# Sheet1.net
KiCad netlist of a schematic drawn in Altium Designer
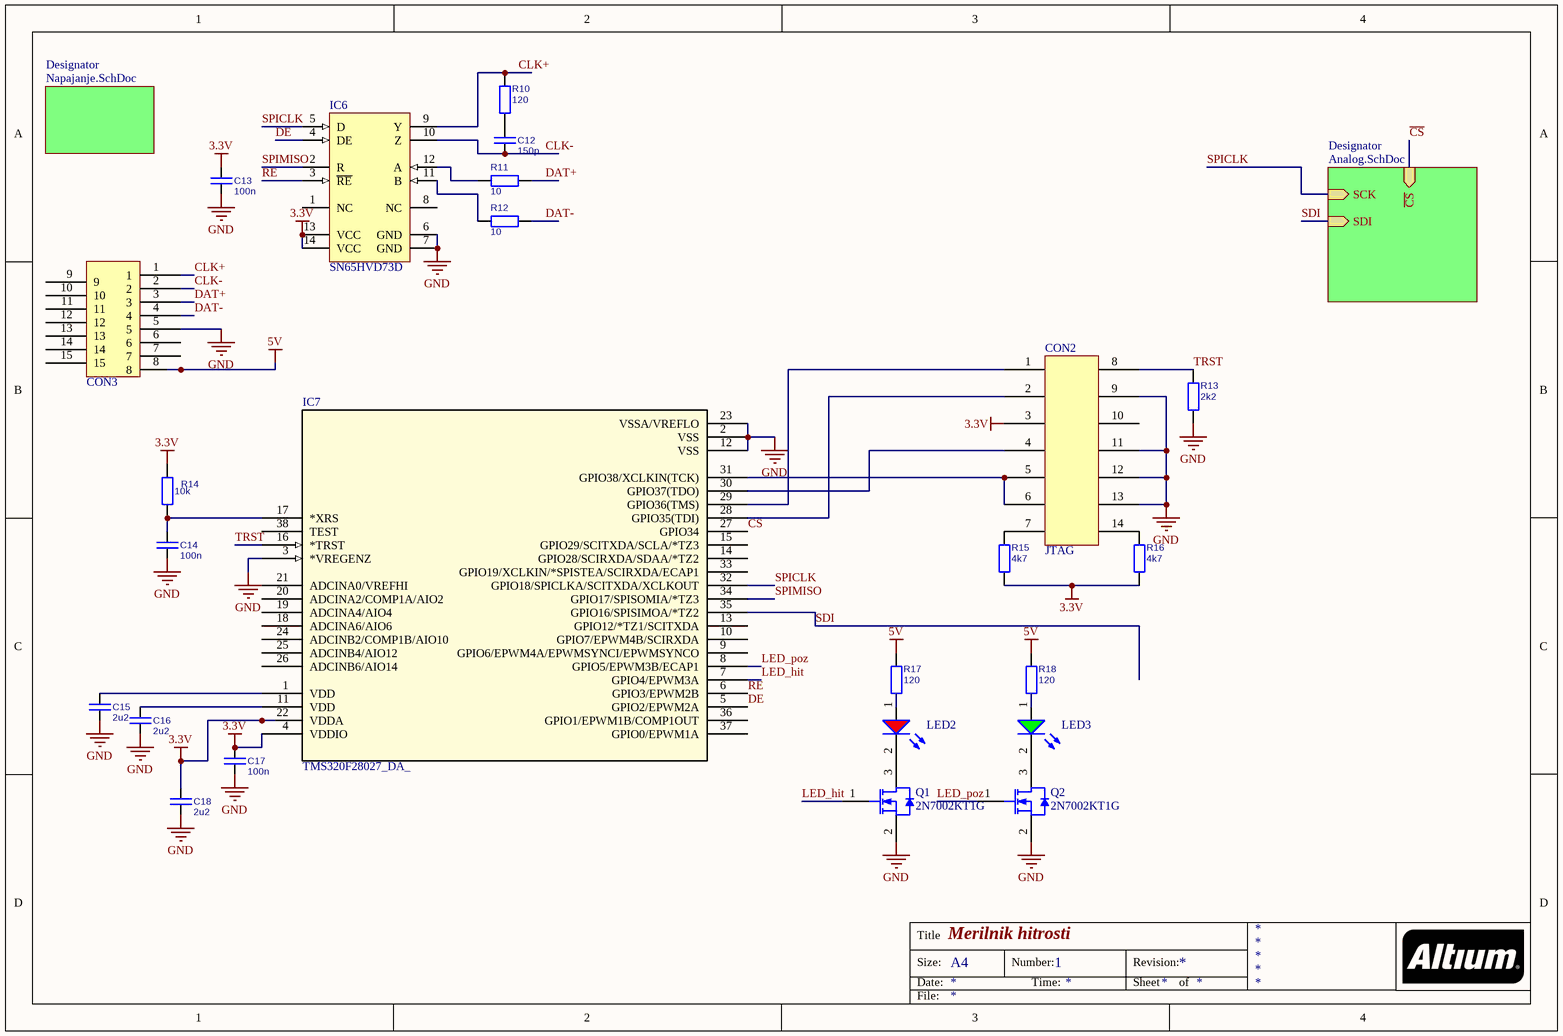
[diagram p0: Sheet1.SchDoc]

(export (version "E")
  (design (tool "Eeschema 10.0.6"))
  (components
    (comp (ref "C12")
      (value "150p")
      (footprint "C0603")
      (description "Capacitor")
      (libsource (lib "General") (part "C"))
    )
    (comp (ref "C13")
      (value "100n")
      (footprint "C0603")
      (description "Capacitor")
      (libsource (lib "General") (part "C"))
    )
    (comp (ref "C14")
      (value "100n")
      (footprint "C0603")
      (description "Capacitor")
      (libsource (lib "General") (part "C"))
    )
    (comp (ref "C15")
      (value "2u2")
      (footprint "C0603")
      (description "Capacitor")
      (libsource (lib "General") (part "C"))
    )
    (comp (ref "C16")
      (value "2u2")
      (footprint "C0603")
      (description "Capacitor")
      (libsource (lib "General") (part "C"))
    )
    (comp (ref "C17")
      (value "100n")
      (footprint "C0603")
      (description "Capacitor")
      (libsource (lib "General") (part "C"))
    )
    (comp (ref "C18")
      (value "2u2")
      (footprint "C0603")
      (description "Capacitor")
      (libsource (lib "General") (part "C"))
    )
    (comp (ref "CON2")
      (value "JTAG")
      (footprint "JTAG micromatch")
      (libsource (lib "2016-11-04_16-51-30") (part "JTAG"))
    )
    (comp (ref "CON3")
      (value "DSUbConector")
      (footprint "DSUB conector")
      (libsource (lib "2016-11-04_16-51-30") (part "DSUbConector"))
    )
    (comp (ref "IC6")
      (value "SN65HVD73D")
      (footprint "D14_N")
      (fields (field (name "MANUFACTURER") "Texas Instruments") (field (name "PARTNUMBER") "SN65HVD55DR"))
      (libsource (lib "Texas Instruments Interface RS-485") (part "SN65HVD55DR"))
    )
    (comp (ref "IC7")
      (value "TMS320F28027_DA_")
      (footprint "TSOP65P810X120-38N")
      (description "Imported")
      (fields (field (name "MANUFACTURER_PART_NUMBER") "tms320f28027_da_38"))
      (libsource (lib "2016-11-04_16-51-30") (part "TMS320F28027_DA_"))
    )
    (comp (ref "LED2")
      (value "150060RS75000")
      (footprint "LED_0603_Red")
      (description "SMD mono-color Chip LED, WL-SMCW, Red")
      (fields
        (field (name "MANUFACTURER") "W黵th Elektronik eiSos GmbH")
        (field (name "CREATED BY") "Christin Otto")
      )
      (libsource (lib "WL-SMCW_rev15b") (part "WL-SMCW 0603  150060RS75000"))
    )
    (comp (ref "LED3")
      (value "150060VS75000")
      (footprint "LED_0603_Bright Green")
      (description "SMD mono-color Chip LED, WL-SMCW, Bright Green")
      (fields
        (field (name "MANUFACTURER") "W黵th Elektronik eiSos GmbH")
        (field (name "CREATED BY") "Christin Otto")
      )
      (libsource (lib "WL-SMCW_rev15b") (part "WL-SMCW 0603  150060VS75000"))
    )
    (comp (ref "Q1")
      (value "2N7002KT1G")
      (footprint "NXP-SOT23_N")
      (description "N-Channel Enhancement Mode Field-Effect Transistor, 50 V, 0.173 A, 3-Pin SOT23, Tape and Reel")
      (libsource (lib "NXP Semiconductors Standard MOSFETs") (part "BSN20,215"))
    )
    (comp (ref "Q2")
      (value "2N7002KT1G")
      (footprint "NXP-SOT23_N")
      (description "N-Channel Enhancement Mode Field-Effect Transistor, 50 V, 0.173 A, 3-Pin SOT23, Tape and Reel")
      (libsource (lib "NXP Semiconductors Standard MOSFETs") (part "BSN20,215"))
    )
    (comp (ref "R10")
      (value "120")
      (footprint "R0603")
      (description "R")
      (libsource (lib "General") (part "R"))
    )
    (comp (ref "R11")
      (value "10")
      (footprint "R0603")
      (description "R")
      (libsource (lib "General") (part "R"))
    )
    (comp (ref "R12")
      (value "10")
      (footprint "R0603")
      (description "R")
      (libsource (lib "General") (part "R"))
    )
    (comp (ref "R13")
      (value "2k2")
      (footprint "R0805")
      (description "R")
      (fields (field (name "Comment") "120"))
      (libsource (lib "General") (part "R"))
    )
    (comp (ref "R14")
      (value "10k")
      (footprint "R0805")
      (description "R")
      (fields (field (name "Comment") "120"))
      (libsource (lib "General") (part "R"))
    )
    (comp (ref "R15")
      (value "4k7")
      (footprint "R0805")
      (description "R")
      (libsource (lib "General") (part "R"))
    )
    (comp (ref "R16")
      (value "4k7")
      (footprint "R0805")
      (description "R")
      (libsource (lib "General") (part "R"))
    )
    (comp (ref "R17")
      (value "120")
      (footprint "R0805")
      (description "R")
      (libsource (lib "General") (part "R"))
    )
    (comp (ref "R18")
      (value "120")
      (footprint "R0805")
      (description "R")
      (libsource (lib "General") (part "R"))
    )
  )
  (nets
    (net (code "1") (name "/CLK+") (class "Default")
      (node (ref "CON3") (pin "1") (pinfunction "1_1") (pintype "passive"))
      (node (ref "IC6") (pin "9") (pinfunction "Y_9") (pintype "tri_state"))
      (node (ref "R10") (pin "1") (pintype "passive"))
    )
    (net (code "2") (name "/CLK-") (class "Default")
      (node (ref "C12") (pin "2") (pinfunction "2_2") (pintype "passive"))
      (node (ref "CON3") (pin "2") (pinfunction "2_2") (pintype "passive"))
      (node (ref "IC6") (pin "10") (pinfunction "Z_10") (pintype "tri_state"))
    )
    (net (code "3") (name "/DAT+") (class "Default")
      (node (ref "CON3") (pin "3") (pinfunction "3_3") (pintype "passive"))
      (node (ref "R11") (pin "1") (pintype "passive"))
    )
    (net (code "4") (name "/DAT-") (class "Default")
      (node (ref "CON3") (pin "4") (pinfunction "4_4") (pintype "passive"))
      (node (ref "R12") (pin "1") (pintype "passive"))
    )
    (net (code "5") (name "/DE") (class "Default")
      (node (ref "IC6") (pin "4") (pinfunction "DE_4") (pintype "input"))
      (node (ref "IC7") (pin "5") (pinfunction "GPIO2/EPWM2A_5") (pintype "passive"))
    )
    (net (code "6") (name "/LED_hit") (class "Default")
      (node (ref "IC7") (pin "7") (pinfunction "GPIO4/EPWM3A_7") (pintype "passive"))
      (node (ref "Q1") (pin "1") (pinfunction "G_1") (pintype "passive"))
    )
    (net (code "7") (name "/LED_poz") (class "Default")
      (node (ref "IC7") (pin "8") (pinfunction "GPIO5/EPWM3B/ECAP1_8") (pintype "passive"))
      (node (ref "Q2") (pin "1") (pinfunction "G_1") (pintype "passive"))
    )
    (net (code "8") (name "/RE") (class "Default")
      (node (ref "IC6") (pin "3") (pinfunction "~{RE}_3") (pintype "input"))
      (node (ref "IC7") (pin "6") (pinfunction "GPIO3/EPWM2B_6") (pintype "passive"))
    )
    (net (code "9") (name "/SDI") (class "Default")
      (node (ref "IC7") (pin "35") (pinfunction "GPIO16/SPISIMOA/*TZ2_35") (pintype "passive"))
    )
    (net (code "10") (name "/SPICLK") (class "Default")
      (node (ref "IC6") (pin "5") (pinfunction "D_5") (pintype "input"))
      (node (ref "IC7") (pin "32") (pinfunction "GPIO18/SPICLKA/SCITXDA/XCLKOUT_32") (pintype "passive"))
    )
    (net (code "11") (name "/SPIMISO") (class "Default")
      (node (ref "IC6") (pin "2") (pinfunction "R_2") (pintype "tri_state"))
      (node (ref "IC7") (pin "34") (pinfunction "GPIO17/SPISOMIA/*TZ3_34") (pintype "passive"))
    )
    (net (code "12") (name "/TRST") (class "Default")
      (node (ref "CON2") (pin "8") (pinfunction "8_8") (pintype "passive"))
      (node (ref "IC7") (pin "16") (pinfunction "*TRST_16") (pintype "input"))
      (node (ref "R13") (pin "2") (pintype "passive"))
    )
    (net (code "13") (name "/~{CS}") (class "Default")
      (node (ref "IC7") (pin "27") (pinfunction "GPIO34_27") (pintype "passive"))
    )
    (net (code "14") (name "3.3V") (class "Default")
      (node (ref "C13") (pin "1") (pinfunction "1_1") (pintype "passive"))
      (node (ref "C17") (pin "1") (pinfunction "1_1") (pintype "passive"))
      (node (ref "C18") (pin "1") (pinfunction "1_1") (pintype "passive"))
      (node (ref "CON2") (pin "3") (pinfunction "3_3") (pintype "passive"))
      (node (ref "IC6") (pin "13") (pinfunction "VCC_13") (pintype "power_in"))
      (node (ref "IC6") (pin "14") (pinfunction "VCC_14") (pintype "power_in"))
      (node (ref "IC7") (pin "22") (pinfunction "VDDA_22") (pintype "power_in"))
      (node (ref "IC7") (pin "4") (pinfunction "VDDIO_4") (pintype "power_in"))
      (node (ref "R14") (pin "1") (pintype "passive"))
      (node (ref "R15") (pin "1") (pintype "passive"))
      (node (ref "R16") (pin "1") (pintype "passive"))
    )
    (net (code "15") (name "5V") (class "Default")
      (node (ref "CON3") (pin "8") (pinfunction "8_8") (pintype "passive"))
      (node (ref "R17") (pin "1") (pintype "passive"))
      (node (ref "R18") (pin "1") (pintype "passive"))
    )
    (net (code "16") (name "GND") (class "Default")
      (node (ref "C13") (pin "2") (pinfunction "2_2") (pintype "passive"))
      (node (ref "C14") (pin "2") (pinfunction "2_2") (pintype "passive"))
      (node (ref "C15") (pin "2") (pinfunction "2_2") (pintype "passive"))
      (node (ref "C16") (pin "2") (pinfunction "2_2") (pintype "passive"))
      (node (ref "C17") (pin "2") (pinfunction "2_2") (pintype "passive"))
      (node (ref "C18") (pin "2") (pinfunction "2_2") (pintype "passive"))
      (node (ref "CON2") (pin "11") (pinfunction "11_11") (pintype "passive"))
      (node (ref "CON2") (pin "12") (pinfunction "12_12") (pintype "passive"))
      (node (ref "CON2") (pin "13") (pinfunction "13_13") (pintype "passive"))
      (node (ref "CON2") (pin "9") (pinfunction "9_9") (pintype "passive"))
      (node (ref "CON3") (pin "5") (pinfunction "5_5") (pintype "passive"))
      (node (ref "IC6") (pin "6") (pinfunction "GND_6") (pintype "power_in"))
      (node (ref "IC6") (pin "7") (pinfunction "GND_7") (pintype "power_in"))
      (node (ref "IC7") (pin "12") (pinfunction "VSS_12") (pintype "power_in"))
      (node (ref "IC7") (pin "2") (pinfunction "VSS_2") (pintype "power_in"))
      (node (ref "IC7") (pin "23") (pinfunction "VSSA/VREFLO_23") (pintype "power_in"))
      (node (ref "IC7") (pin "3") (pinfunction "*VREGENZ_3") (pintype "input"))
      (node (ref "Q1") (pin "2") (pinfunction "S_2") (pintype "passive"))
      (node (ref "Q2") (pin "2") (pinfunction "S_2") (pintype "passive"))
      (node (ref "R13") (pin "1") (pintype "passive"))
    )
    (net (code "17") (name "Net-(C12-Pad1)") (class "Default")
      (node (ref "C12") (pin "1") (pinfunction "1_1") (pintype "passive"))
      (node (ref "R10") (pin "2") (pintype "passive"))
    )
    (net (code "18") (name "Net-(C15-Pad1)") (class "Default")
      (node (ref "C15") (pin "1") (pinfunction "1_1") (pintype "passive"))
      (node (ref "IC7") (pin "1") (pinfunction "VDD_1") (pintype "power_in"))
    )
    (net (code "19") (name "Net-(C16-Pad1)") (class "Default")
      (node (ref "C16") (pin "1") (pinfunction "1_1") (pintype "passive"))
      (node (ref "IC7") (pin "11") (pinfunction "VDD_11") (pintype "power_in"))
    )
    (net (code "20") (name "Net-(CON2-Pad7)") (class "Default")
      (node (ref "CON2") (pin "7") (pinfunction "7_7") (pintype "passive"))
      (node (ref "R15") (pin "2") (pintype "passive"))
    )
    (net (code "21") (name "Net-(CON2-Pad14)") (class "Default")
      (node (ref "CON2") (pin "14") (pinfunction "14_14") (pintype "passive"))
      (node (ref "R16") (pin "2") (pintype "passive"))
    )
    (net (code "22") (name "Net-(IC6-A)") (class "Default")
      (node (ref "IC6") (pin "12") (pinfunction "A_12") (pintype "input"))
      (node (ref "R11") (pin "2") (pintype "passive"))
    )
    (net (code "23") (name "Net-(IC6-B)") (class "Default")
      (node (ref "IC6") (pin "11") (pinfunction "B_11") (pintype "input"))
      (node (ref "R12") (pin "2") (pintype "passive"))
    )
    (net (code "24") (name "Net-(IC7-*XRS)") (class "Default")
      (node (ref "C14") (pin "1") (pinfunction "1_1") (pintype "passive"))
      (node (ref "IC7") (pin "17") (pinfunction "*XRS_17") (pintype "passive"))
      (node (ref "R14") (pin "2") (pintype "passive"))
    )
    (net (code "25") (name "Net-(IC7-GPIO35(TDI))") (class "Default")
      (node (ref "CON2") (pin "2") (pinfunction "2_2") (pintype "passive"))
      (node (ref "IC7") (pin "28") (pinfunction "GPIO35(TDI)_28") (pintype "passive"))
    )
    (net (code "26") (name "Net-(IC7-GPIO36(TMS))") (class "Default")
      (node (ref "CON2") (pin "1") (pinfunction "1_1") (pintype "passive"))
      (node (ref "IC7") (pin "29") (pinfunction "GPIO36(TMS)_29") (pintype "passive"))
    )
    (net (code "27") (name "Net-(IC7-GPIO37(TDO))") (class "Default")
      (node (ref "CON2") (pin "4") (pinfunction "4_4") (pintype "passive"))
      (node (ref "IC7") (pin "30") (pinfunction "GPIO37(TDO)_30") (pintype "passive"))
    )
    (net (code "28") (name "Net-(IC7-GPIO38{slash}XCLKIN(TCK))") (class "Default")
      (node (ref "CON2") (pin "5") (pinfunction "5_5") (pintype "passive"))
      (node (ref "CON2") (pin "6") (pinfunction "6_6") (pintype "passive"))
      (node (ref "IC7") (pin "31") (pinfunction "GPIO38/XCLKIN(TCK)_31") (pintype "passive"))
    )
    (net (code "29") (name "Net-(LED2-A)") (class "Default")
      (node (ref "LED2") (pin "1") (pinfunction "A_1") (pintype "passive"))
      (node (ref "R17") (pin "2") (pintype "passive"))
    )
    (net (code "30") (name "Net-(LED2-C)") (class "Default")
      (node (ref "LED2") (pin "2") (pinfunction "C_2") (pintype "passive"))
      (node (ref "Q1") (pin "3") (pinfunction "D_3") (pintype "passive"))
    )
    (net (code "31") (name "Net-(LED3-A)") (class "Default")
      (node (ref "LED3") (pin "1") (pinfunction "A_1") (pintype "passive"))
      (node (ref "R18") (pin "2") (pintype "passive"))
    )
    (net (code "32") (name "Net-(LED3-C)") (class "Default")
      (node (ref "LED3") (pin "2") (pinfunction "C_2") (pintype "passive"))
      (node (ref "Q2") (pin "3") (pinfunction "D_3") (pintype "passive"))
    )
    (net (code "33") (name "unconnected-(CON2-Pad10)") (class "Default")
      (node (ref "CON2") (pin "10") (pinfunction "10_10") (pintype "passive"))
    )
    (net (code "34") (name "unconnected-(CON3-Pad6)") (class "Default")
      (node (ref "CON3") (pin "6") (pinfunction "6_6") (pintype "passive"))
    )
    (net (code "35") (name "unconnected-(CON3-Pad7)") (class "Default")
      (node (ref "CON3") (pin "7") (pinfunction "7_7") (pintype "passive"))
    )
    (net (code "36") (name "unconnected-(CON3-Pad9)") (class "Default")
      (node (ref "CON3") (pin "9") (pinfunction "9_9") (pintype "passive"))
    )
    (net (code "37") (name "unconnected-(CON3-Pad10)") (class "Default")
      (node (ref "CON3") (pin "10") (pinfunction "10_10") (pintype "passive"))
    )
    (net (code "38") (name "unconnected-(CON3-Pad11)") (class "Default")
      (node (ref "CON3") (pin "11") (pinfunction "11_11") (pintype "passive"))
    )
    (net (code "39") (name "unconnected-(CON3-Pad12)") (class "Default")
      (node (ref "CON3") (pin "12") (pinfunction "12_12") (pintype "passive"))
    )
    (net (code "40") (name "unconnected-(CON3-Pad13)") (class "Default")
      (node (ref "CON3") (pin "13") (pinfunction "13_13") (pintype "passive"))
    )
    (net (code "41") (name "unconnected-(CON3-Pad14)") (class "Default")
      (node (ref "CON3") (pin "14") (pinfunction "14_14") (pintype "passive"))
    )
    (net (code "42") (name "unconnected-(CON3-Pad15)") (class "Default")
      (node (ref "CON3") (pin "15") (pinfunction "15_15") (pintype "passive"))
    )
    (net (code "43") (name "unconnected-(IC6-NC-Pad1)") (class "Default")
      (node (ref "IC6") (pin "1") (pinfunction "NC_1") (pintype "passive"))
    )
    (net (code "44") (name "unconnected-(IC6-NC-Pad8)") (class "Default")
      (node (ref "IC6") (pin "8") (pinfunction "NC_8") (pintype "passive"))
    )
    (net (code "45") (name "unconnected-(IC7-ADCINA0{slash}VREFHI-Pad21)") (class "Default")
      (node (ref "IC7") (pin "21") (pinfunction "ADCINA0/VREFHI_21") (pintype "passive"))
    )
    (net (code "46") (name "unconnected-(IC7-ADCINA2{slash}COMP1A{slash}AIO2-Pad20)") (class "Default")
      (node (ref "IC7") (pin "20") (pinfunction "ADCINA2/COMP1A/AIO2_20") (pintype "passive"))
    )
    (net (code "47") (name "unconnected-(IC7-ADCINA4{slash}AIO4-Pad19)") (class "Default")
      (node (ref "IC7") (pin "19") (pinfunction "ADCINA4/AIO4_19") (pintype "passive"))
    )
    (net (code "48") (name "unconnected-(IC7-ADCINA6{slash}AIO6-Pad18)") (class "Default")
      (node (ref "IC7") (pin "18") (pinfunction "ADCINA6/AIO6_18") (pintype "passive"))
    )
    (net (code "49") (name "unconnected-(IC7-ADCINB2{slash}COMP1B{slash}AIO10-Pad24)") (class "Default")
      (node (ref "IC7") (pin "24") (pinfunction "ADCINB2/COMP1B/AIO10_24") (pintype "passive"))
    )
    (net (code "50") (name "unconnected-(IC7-ADCINB4{slash}AIO12-Pad25)") (class "Default")
      (node (ref "IC7") (pin "25") (pinfunction "ADCINB4/AIO12_25") (pintype "passive"))
    )
    (net (code "51") (name "unconnected-(IC7-ADCINB6{slash}AIO14-Pad26)") (class "Default")
      (node (ref "IC7") (pin "26") (pinfunction "ADCINB6/AIO14_26") (pintype "passive"))
    )
    (net (code "52") (name "unconnected-(IC7-GPIO0{slash}EPWM1A-Pad37)") (class "Default")
      (node (ref "IC7") (pin "37") (pinfunction "GPIO0/EPWM1A_37") (pintype "passive"))
    )
    (net (code "53") (name "unconnected-(IC7-GPIO1{slash}EPWM1B{slash}COMP1OUT-Pad36)") (class "Default")
      (node (ref "IC7") (pin "36") (pinfunction "GPIO1/EPWM1B/COMP1OUT_36") (pintype "passive"))
    )
    (net (code "54") (name "unconnected-(IC7-GPIO6{slash}EPWM4A{slash}EPWMSYNCI{slash}EPWMSYNCO-Pad9)") (class "Default")
      (node (ref "IC7") (pin "9") (pinfunction "GPIO6/EPWM4A/EPWMSYNCI/EPWMSYNCO_9") (pintype "passive"))
    )
    (net (code "55") (name "unconnected-(IC7-GPIO7{slash}EPWM4B{slash}SCIRXDA-Pad10)") (class "Default")
      (node (ref "IC7") (pin "10") (pinfunction "GPIO7/EPWM4B/SCIRXDA_10") (pintype "passive"))
    )
    (net (code "56") (name "unconnected-(IC7-GPIO12{slash}*TZ1{slash}SCITXDA-Pad13)") (class "Default")
      (node (ref "IC7") (pin "13") (pinfunction "GPIO12/*TZ1/SCITXDA_13") (pintype "passive"))
    )
    (net (code "57") (name "unconnected-(IC7-GPIO19{slash}XCLKIN{slash}*SPISTEA{slash}SCIRXDA{slash}ECAP1-Pad33)") (class "Default")
      (node (ref "IC7") (pin "33") (pinfunction "GPIO19/XCLKIN/*SPISTEA/SCIRXDA/ECAP1_33") (pintype "passive"))
    )
    (net (code "58") (name "unconnected-(IC7-GPIO28{slash}SCIRXDA{slash}SDAA{slash}*TZ2-Pad14)") (class "Default")
      (node (ref "IC7") (pin "14") (pinfunction "GPIO28/SCIRXDA/SDAA/*TZ2_14") (pintype "passive"))
    )
    (net (code "59") (name "unconnected-(IC7-GPIO29{slash}SCITXDA{slash}SCLA{slash}*TZ3-Pad15)") (class "Default")
      (node (ref "IC7") (pin "15") (pinfunction "GPIO29/SCITXDA/SCLA/*TZ3_15") (pintype "passive"))
    )
    (net (code "60") (name "unconnected-(IC7-TEST-Pad38)") (class "Default")
      (node (ref "IC7") (pin "38") (pinfunction "TEST_38") (pintype "passive"))
    )
  )
)
